# User_Interfaces.net
KiCad netlist of a schematic drawn in Altium Designer
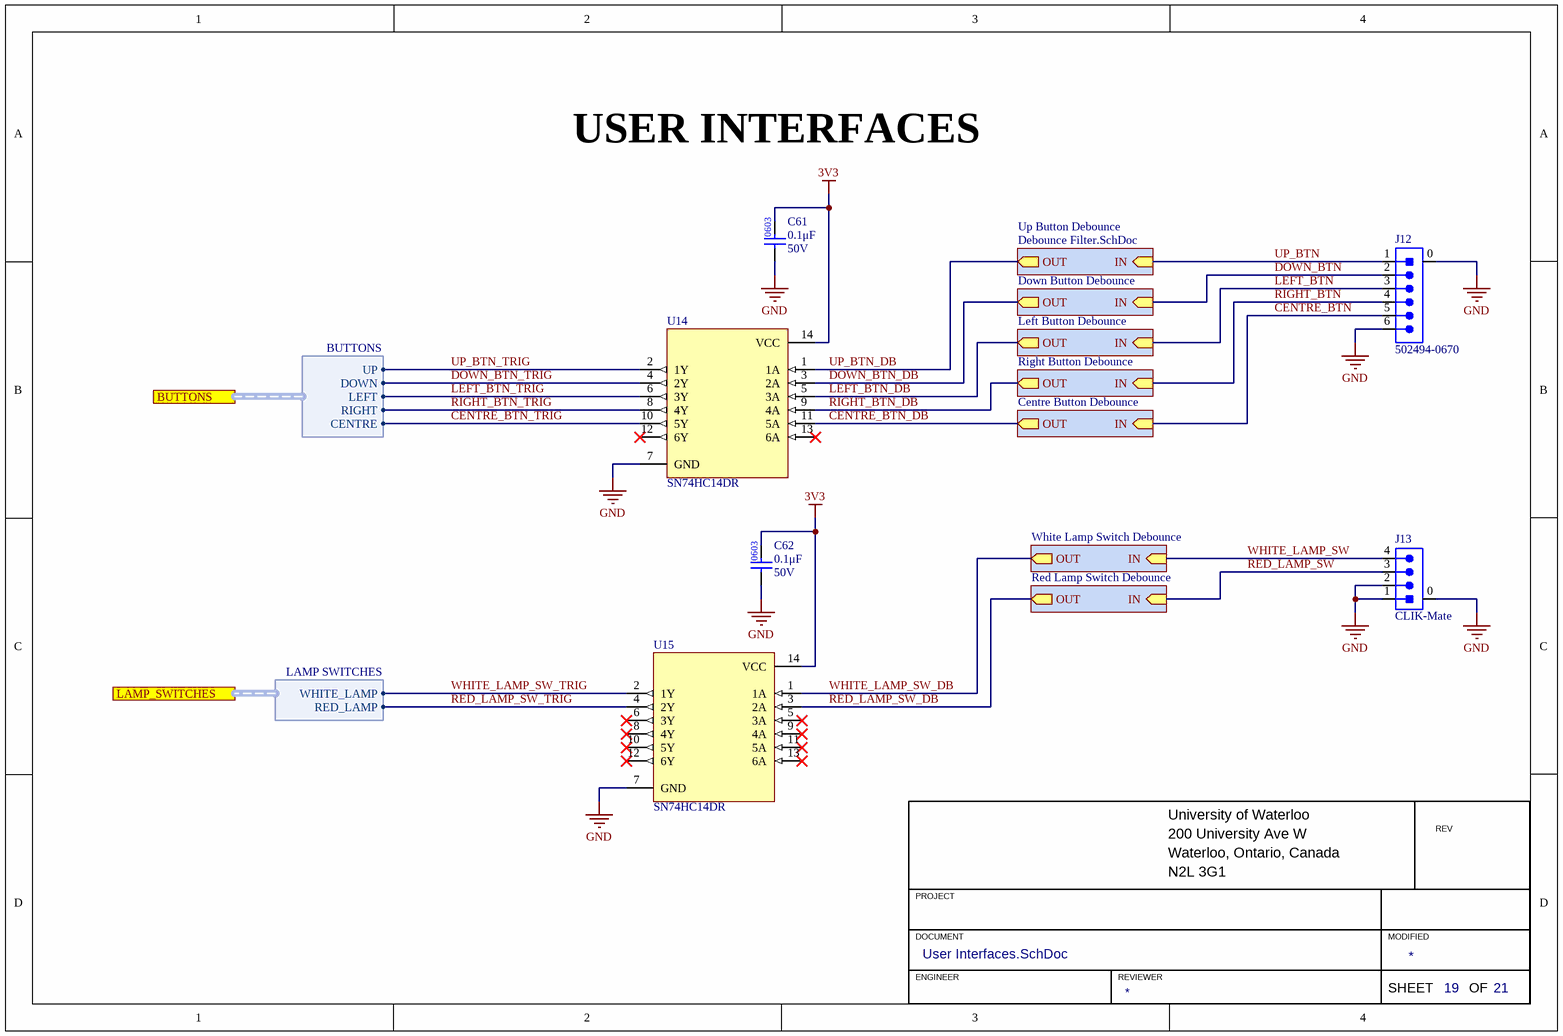
[diagram p0: User Interfaces.SchDoc]

(export (version "E")
  (design (tool "Eeschema 10.0.6"))
  (components
    (comp (ref "C61")
      (value "0.1μF")
      (footprint "CAP0603")
      (description "CAP CER 0.1UF 50V X7R 0603")
      (fields (field (name "VOLTAGE RATING") "50V") (field (name "Comment") "CAP_0.1uF_50V_0603"))
      (libsource (lib "Personal_Schematic_Library_2022") (part "CAP_0.1uF_50V_0603"))
    )
    (comp (ref "C62")
      (value "0.1μF")
      (footprint "CAP0603")
      (description "CAP CER 0.1UF 50V X7R 0603")
      (fields (field (name "VOLTAGE RATING") "50V") (field (name "Comment") "CAP_0.1uF_50V_0603"))
      (libsource (lib "Personal_Schematic_Library_2022") (part "CAP_0.1uF_50V_0603"))
    )
    (comp (ref "J12")
      (value "CON_6M_SM_RA")
      (footprint "MOLEX-5024940670")
      (description "CONN HEADER SMD RIGHT ANGLE 2MM PITCH")
      (fields (field (name "MANUFACTURER PART NUMBER 1") "502494-0670"))
      (libsource (lib "Personal_Schematic_Library_2022") (part "CON_6M_SM_RA"))
    )
    (comp (ref "J13")
      (value "CON_4M_SM_RA")
      (footprint "MOLEX-5025850470")
      (description "CONN HEADER SMD RIGHT ANGLE 1.5 MM PITCH")
      (fields (field (name "FAMILY") "CLIK-Mate"))
      (libsource (lib "Personal_Schematic_Library_2022") (part "CON_4M_SM_RA"))
    )
    (comp (ref "U14")
      (value "SN74HC14DR")
      (footprint "TI_14-SOIC")
      (description "IC INVERT SCHMITT 6CH 1IN 14SOIC")
      (libsource (lib "Personal_Schematic_Library_2022") (part "SN74HC14DR"))
    )
    (comp (ref "U15")
      (value "SN74HC14DR")
      (footprint "TI_14-SOIC")
      (description "IC INVERT SCHMITT 6CH 1IN 14SOIC")
      (libsource (lib "Personal_Schematic_Library_2022") (part "SN74HC14DR"))
    )
  )
  (nets
    (net (code "4") (name "/CENTRE_BTN") (class "Default")
      (node (ref "J12") (pin "5") (pinfunction "5_5") (pintype "passive"))
    )
    (net (code "5") (name "/CENTRE_BTN_DB") (class "Default")
      (node (ref "U14") (pin "11") (pinfunction "5A_11") (pintype "input"))
    )
    (net (code "6") (name "/CENTRE_BTN_TRIG") (class "Default")
      (node (ref "U14") (pin "10") (pinfunction "5Y_10") (pintype "output"))
    )
    (net (code "7") (name "/DOWN_BTN") (class "Default")
      (node (ref "J12") (pin "2") (pinfunction "2_2") (pintype "passive"))
    )
    (net (code "8") (name "/DOWN_BTN_DB") (class "Default")
      (node (ref "U14") (pin "3") (pinfunction "2A_3") (pintype "input"))
    )
    (net (code "9") (name "/DOWN_BTN_TRIG") (class "Default")
      (node (ref "U14") (pin "4") (pinfunction "2Y_4") (pintype "output"))
    )
    (net (code "10") (name "/LEFT_BTN") (class "Default")
      (node (ref "J12") (pin "3") (pinfunction "3_3") (pintype "passive"))
    )
    (net (code "11") (name "/LEFT_BTN_DB") (class "Default")
      (node (ref "U14") (pin "5") (pinfunction "3A_5") (pintype "input"))
    )
    (net (code "12") (name "/LEFT_BTN_TRIG") (class "Default")
      (node (ref "U14") (pin "6") (pinfunction "3Y_6") (pintype "output"))
    )
    (net (code "13") (name "/RED_LAMP_SW") (class "Default")
      (node (ref "J13") (pin "3") (pinfunction "3_3") (pintype "passive"))
    )
    (net (code "14") (name "/RED_LAMP_SW_DB") (class "Default")
      (node (ref "U15") (pin "3") (pinfunction "2A_3") (pintype "input"))
    )
    (net (code "15") (name "/RED_LAMP_SW_TRIG") (class "Default")
      (node (ref "U15") (pin "4") (pinfunction "2Y_4") (pintype "output"))
    )
    (net (code "16") (name "/RIGHT_BTN") (class "Default")
      (node (ref "J12") (pin "4") (pinfunction "4_4") (pintype "passive"))
    )
    (net (code "17") (name "/RIGHT_BTN_DB") (class "Default")
      (node (ref "U14") (pin "9") (pinfunction "4A_9") (pintype "input"))
    )
    (net (code "18") (name "/RIGHT_BTN_TRIG") (class "Default")
      (node (ref "U14") (pin "8") (pinfunction "4Y_8") (pintype "output"))
    )
    (net (code "19") (name "/UP_BTN") (class "Default")
      (node (ref "J12") (pin "1") (pinfunction "1_1") (pintype "passive"))
    )
    (net (code "20") (name "/UP_BTN_DB") (class "Default")
      (node (ref "U14") (pin "1") (pinfunction "1A_1") (pintype "input"))
    )
    (net (code "21") (name "/UP_BTN_TRIG") (class "Default")
      (node (ref "U14") (pin "2") (pinfunction "1Y_2") (pintype "output"))
    )
    (net (code "22") (name "/WHITE_LAMP_SW") (class "Default")
      (node (ref "J13") (pin "4") (pinfunction "4_4") (pintype "passive"))
    )
    (net (code "23") (name "/WHITE_LAMP_SW_DB") (class "Default")
      (node (ref "U15") (pin "1") (pinfunction "1A_1") (pintype "input"))
    )
    (net (code "24") (name "/WHITE_LAMP_SW_TRIG") (class "Default")
      (node (ref "U15") (pin "2") (pinfunction "1Y_2") (pintype "output"))
    )
    (net (code "27") (name "3V3") (class "Default")
      (node (ref "C61") (pin "2") (pinfunction "2_2") (pintype "passive"))
      (node (ref "C62") (pin "2") (pinfunction "2_2") (pintype "passive"))
      (node (ref "U14") (pin "14") (pinfunction "VCC_14") (pintype "power_in"))
      (node (ref "U15") (pin "14") (pinfunction "VCC_14") (pintype "power_in"))
    )
    (net (code "28") (name "GND") (class "Default")
      (node (ref "C61") (pin "1") (pinfunction "1_1") (pintype "passive"))
      (node (ref "C62") (pin "1") (pinfunction "1_1") (pintype "passive"))
      (node (ref "J12") (pin "0") (pinfunction "0_0") (pintype "passive"))
      (node (ref "J12") (pin "6") (pinfunction "6_6") (pintype "passive"))
      (node (ref "J13") (pin "0") (pinfunction "0_0") (pintype "passive"))
      (node (ref "J13") (pin "1") (pinfunction "1_1") (pintype "passive"))
      (node (ref "J13") (pin "2") (pinfunction "2_2") (pintype "passive"))
      (node (ref "U14") (pin "7") (pinfunction "GND_7") (pintype "power_in"))
      (node (ref "U15") (pin "7") (pinfunction "GND_7") (pintype "power_in"))
    )
    (net (code "29") (name "unconnected-(U14-6A-Pad13)") (class "Default")
      (node (ref "U14") (pin "13") (pinfunction "6A_13") (pintype "input+no_connect"))
    )
    (net (code "30") (name "unconnected-(U14-6Y-Pad12)") (class "Default")
      (node (ref "U14") (pin "12") (pinfunction "6Y_12") (pintype "output+no_connect"))
    )
    (net (code "31") (name "unconnected-(U15-3A-Pad5)") (class "Default")
      (node (ref "U15") (pin "5") (pinfunction "3A_5") (pintype "input+no_connect"))
    )
    (net (code "32") (name "unconnected-(U15-3Y-Pad6)") (class "Default")
      (node (ref "U15") (pin "6") (pinfunction "3Y_6") (pintype "output+no_connect"))
    )
    (net (code "33") (name "unconnected-(U15-4A-Pad9)") (class "Default")
      (node (ref "U15") (pin "9") (pinfunction "4A_9") (pintype "input+no_connect"))
    )
    (net (code "34") (name "unconnected-(U15-4Y-Pad8)") (class "Default")
      (node (ref "U15") (pin "8") (pinfunction "4Y_8") (pintype "output+no_connect"))
    )
    (net (code "35") (name "unconnected-(U15-5A-Pad11)") (class "Default")
      (node (ref "U15") (pin "11") (pinfunction "5A_11") (pintype "input+no_connect"))
    )
    (net (code "36") (name "unconnected-(U15-5Y-Pad10)") (class "Default")
      (node (ref "U15") (pin "10") (pinfunction "5Y_10") (pintype "output+no_connect"))
    )
    (net (code "37") (name "unconnected-(U15-6A-Pad13)") (class "Default")
      (node (ref "U15") (pin "13") (pinfunction "6A_13") (pintype "input+no_connect"))
    )
    (net (code "38") (name "unconnected-(U15-6Y-Pad12)") (class "Default")
      (node (ref "U15") (pin "12") (pinfunction "6Y_12") (pintype "output+no_connect"))
    )
  )
)
